# ESIMA_E-Meter_LCD.net
KiCad netlist of a schematic drawn in Altium Designer
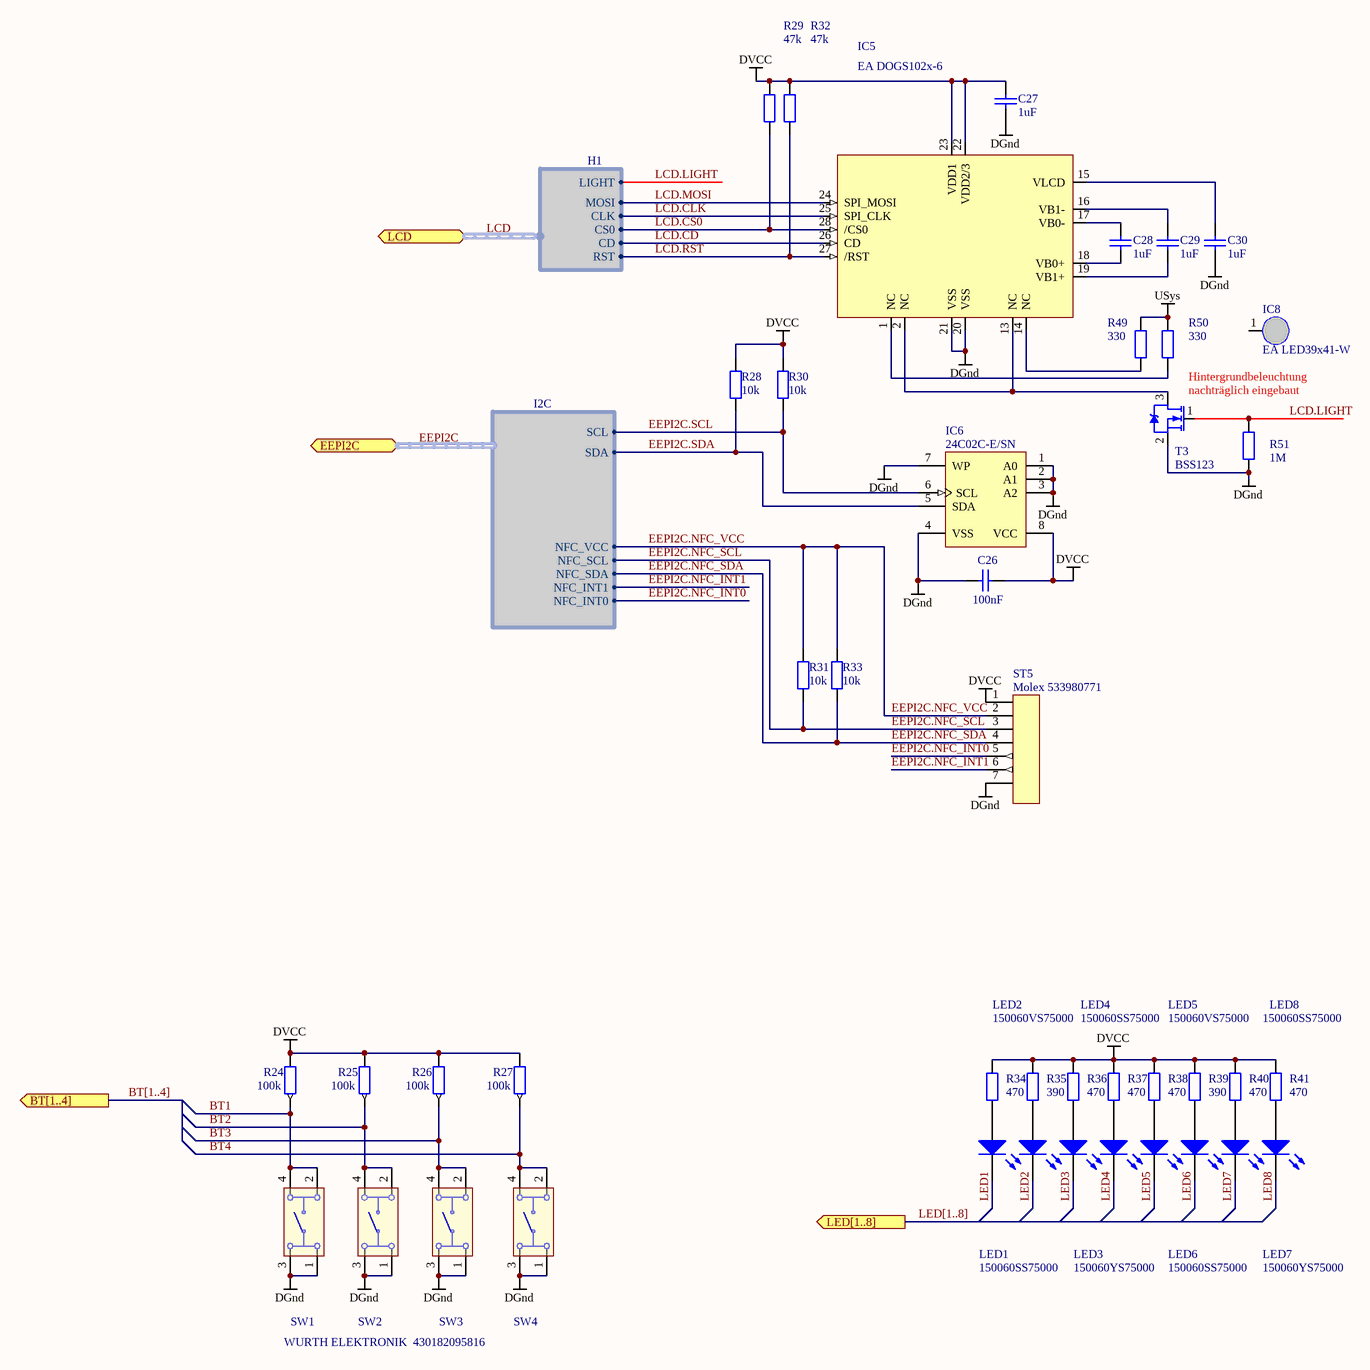
[diagram p0: ESIMA E-Meter_LCD.SchDoc]

(export (version "E")
  (design (tool "Eeschema 10.0.6"))
  (components
    (comp (ref "C26")
      (value "100nF")
      (footprint "CAPC1608N")
      (description "CAPC1608 (C0603)")
      (libsource (lib "JM_Kondensatoren") (part "CAPC1608 (C0603)"))
    )
    (comp (ref "C27")
      (value "1uF")
      (footprint "CAPC2012N")
      (description "CAPC2012 (C0805)")
      (libsource (lib "JM_Kondensatoren") (part "CAPC2012 (C0805)"))
    )
    (comp (ref "C28")
      (value "1uF")
      (footprint "CAPC2012N")
      (description "CAPC2012 (C0805)")
      (libsource (lib "JM_Kondensatoren") (part "CAPC2012 (C0805)"))
    )
    (comp (ref "C29")
      (value "1uF")
      (footprint "CAPC2012N")
      (description "CAPC2012 (C0805)")
      (libsource (lib "JM_Kondensatoren") (part "CAPC2012 (C0805)"))
    )
    (comp (ref "C30")
      (value "1uF")
      (footprint "CAPC2012N")
      (description "CAPC2012 (C0805)")
      (libsource (lib "JM_Kondensatoren") (part "CAPC2012 (C0805)"))
    )
    (comp (ref "IC5")
      (value "EA DOGS102x-6")
      (footprint "EA DOGS102x-6")
      (description "LCD Graphic Display 102*64 Dots SPI-Interface")
      (libsource (lib "JM_Halbleiter") (part "EA DOGS102x-6"))
    )
    (comp (ref "IC6")
      (value "24C02C-E/SN")
      (footprint "SOIC-SN8_N")
      (description "2Kbit, 400kHz, 5V, I2C Serial EEPROM, 8-Pin SOIC 150mil, Extended Temperature")
      (libsource (lib "Microchip EEPROM I2C Serial") (part "24C02C-E/SN"))
    )
    (comp (ref "IC8")
      (value "EA LED39x41-W")
      (description "LCD-Hintergrundbeleuchtung, Part von EA DOGS102x-6")
      (libsource (lib "JM_Elektromechanik") (part "Passmarke 1mm"))
    )
    (comp (ref "LED1")
      (value "150060SS75000")
      (footprint "0603")
      (description "LED, 0603, SUP. ROT, 60MCD, 630NM")
      (libsource (lib "WL-SMCW") (part "WL-SMCW 0603  150060SS75000"))
    )
    (comp (ref "LED2")
      (value "150060VS75000")
      (footprint "0603")
      (description "LED, 0603, GRÜN, 40MCD, 570NM")
      (libsource (lib "WL-SMCW") (part "WL-SMCW 0603  150060VS75000"))
    )
    (comp (ref "LED3")
      (value "150060YS75000")
      (footprint "0603")
      (description "LED, 0603, GELB, 120MCD, 590NM")
      (libsource (lib "WL-SMCW") (part "WL-SMCW 0603  150060YS75000"))
    )
    (comp (ref "LED4")
      (value "150060SS75000")
      (footprint "0603")
      (description "LED, 0603, SUP. ROT, 60MCD, 630NM")
      (libsource (lib "WL-SMCW") (part "WL-SMCW 0603  150060SS75000"))
    )
    (comp (ref "LED5")
      (value "150060VS75000")
      (footprint "0603")
      (description "LED, 0603, SUP. ROT, 60MCD, 630NM")
      (libsource (lib "WL-SMCW") (part "WL-SMCW 0603  150060VS75000"))
    )
    (comp (ref "LED6")
      (value "150060SS75000")
      (footprint "0603")
      (description "LED, 0603, GRÜN, 40MCD, 570NM")
      (libsource (lib "WL-SMCW") (part "WL-SMCW 0603  150060SS75000"))
    )
    (comp (ref "LED7")
      (value "150060YS75000")
      (footprint "0603")
      (description "LED, 0603, GELB, 120MCD, 590NM")
      (libsource (lib "WL-SMCW") (part "WL-SMCW 0603  150060YS75000"))
    )
    (comp (ref "LED8")
      (value "150060SS75000")
      (footprint "0603")
      (description "LED, 0603, SUP. ROT, 60MCD, 630NM")
      (libsource (lib "WL-SMCW") (part "WL-SMCW 0603  150060SS75000"))
    )
    (comp (ref "R24")
      (value "100k")
      (footprint "RESC1608N")
      (description "RESC1608 (R0603)")
      (libsource (lib "") (part "RESC1608 (R0603)_1"))
    )
    (comp (ref "R25")
      (value "100k")
      (footprint "RESC1608N")
      (description "RESC1608 (R0603)")
      (libsource (lib "") (part "RESC1608 (R0603)_1"))
    )
    (comp (ref "R26")
      (value "100k")
      (footprint "RESC1608N")
      (description "RESC1608 (R0603)")
      (libsource (lib "") (part "RESC1608 (R0603)_1"))
    )
    (comp (ref "R27")
      (value "100k")
      (footprint "RESC1608N")
      (description "RESC1608 (R0603)")
      (libsource (lib "") (part "RESC1608 (R0603)_1"))
    )
    (comp (ref "R28")
      (value "10k")
      (footprint "RESC1608N")
      (description "RESC1608 (R0603)")
      (libsource (lib "JM_Widerstaende") (part "RESC1608 (R0603)"))
    )
    (comp (ref "R29")
      (value "47k")
      (footprint "RESC1608N")
      (description "RESC1608 (R0603)")
      (libsource (lib "") (part "RESC1608 (R0603)_3"))
    )
    (comp (ref "R30")
      (value "10k")
      (footprint "RESC1608N")
      (description "RESC1608 (R0603)")
      (libsource (lib "JM_Widerstaende") (part "RESC1608 (R0603)"))
    )
    (comp (ref "R31")
      (value "10k")
      (footprint "RESC1608N")
      (description "RESC1608 (R0603)")
      (libsource (lib "JM_Widerstaende") (part "RESC1608 (R0603)"))
    )
    (comp (ref "R32")
      (value "47k")
      (footprint "RESC1608N")
      (description "RESC1608 (R0603)")
      (libsource (lib "") (part "RESC1608 (R0603)_3"))
    )
    (comp (ref "R33")
      (value "10k")
      (footprint "RESC1608N")
      (description "RESC1608 (R0603)")
      (libsource (lib "JM_Widerstaende") (part "RESC1608 (R0603)"))
    )
    (comp (ref "R34")
      (value "470")
      (footprint "RESC1608N")
      (description "RESC1608 (R0603)")
      (libsource (lib "") (part "RESC1608 (R0603)_2"))
    )
    (comp (ref "R35")
      (value "390")
      (footprint "RESC1608N")
      (description "RESC1608 (R0603)")
      (libsource (lib "") (part "RESC1608 (R0603)_2"))
    )
    (comp (ref "R36")
      (value "470")
      (footprint "RESC1608N")
      (description "RESC1608 (R0603)")
      (libsource (lib "") (part "RESC1608 (R0603)_2"))
    )
    (comp (ref "R37")
      (value "470")
      (footprint "RESC1608N")
      (description "RESC1608 (R0603)")
      (libsource (lib "") (part "RESC1608 (R0603)_2"))
    )
    (comp (ref "R38")
      (value "470")
      (footprint "RESC1608N")
      (description "RESC1608 (R0603)")
      (libsource (lib "") (part "RESC1608 (R0603)_2"))
    )
    (comp (ref "R39")
      (value "390")
      (footprint "RESC1608N")
      (description "RESC1608 (R0603)")
      (libsource (lib "") (part "RESC1608 (R0603)_2"))
    )
    (comp (ref "R40")
      (value "470")
      (footprint "RESC1608N")
      (description "RESC1608 (R0603)")
      (libsource (lib "") (part "RESC1608 (R0603)_2"))
    )
    (comp (ref "R41")
      (value "470")
      (footprint "RESC1608N")
      (description "RESC1608 (R0603)")
      (libsource (lib "") (part "RESC1608 (R0603)_2"))
    )
    (comp (ref "R49")
      (value "330")
      (footprint "RESC1608N")
      (description "RESC1608 (R0603)")
      (libsource (lib "") (part "RESC1608 (R0603)_3"))
    )
    (comp (ref "R50")
      (value "330")
      (footprint "RESC1608N")
      (description "RESC1608 (R0603)")
      (libsource (lib "") (part "RESC1608 (R0603)_3"))
    )
    (comp (ref "R51")
      (value "1M")
      (footprint "RESC1608N")
      (description "RESC1608 (R0603)")
      (libsource (lib "") (part "RESC1608 (R0603)_3"))
    )
    (comp (ref "ST5")
      (value "Molex 533980771")
      (footprint "Molex 533980771")
      (description "Molex Pico 7Pol Blade SMD gerade 533980771")
      (libsource (lib "JM_Elektromechanik") (part "Molex 533980771"))
    )
    (comp (ref "SW1")
      (value "WURTH ELEKTRONIK  430182095816")
      (footprint "430152130826")
      (description "WS-TASV SMD Tact Switch 6X6 mm")
      (fields
        (field (name "MANUFACTURER") "Würth Elektronik eiSos GmbH & Co.KG")
        (field (name "PARTNO") "430152130826")
        (field (name "CREAT BY") "Karrer Zheng")
      )
      (libsource (lib "Kurzhubtaster") (part "WE-Tact Switches WS-TASV 430152130826"))
    )
    (comp (ref "SW2")
      (value "WURTH ELEKTRONIK  430182095816")
      (footprint "430152130826")
      (description "WS-TASV SMD Tact Switch 6X6 mm")
      (fields
        (field (name "MANUFACTURER") "Würth Elektronik eiSos GmbH & Co.KG")
        (field (name "PARTNO") "430152130826")
        (field (name "CREAT BY") "Karrer Zheng")
      )
      (libsource (lib "Kurzhubtaster") (part "WE-Tact Switches WS-TASV 430152130826"))
    )
    (comp (ref "SW3")
      (value "WURTH ELEKTRONIK  430182095816")
      (footprint "430152130826")
      (description "WS-TASV SMD Tact Switch 6X6 mm")
      (fields
        (field (name "MANUFACTURER") "Würth Elektronik eiSos GmbH & Co.KG")
        (field (name "PARTNO") "430152130826")
        (field (name "CREAT BY") "Karrer Zheng")
      )
      (libsource (lib "Kurzhubtaster") (part "WE-Tact Switches WS-TASV 430152130826"))
    )
    (comp (ref "SW4")
      (value "WURTH ELEKTRONIK  430182095816")
      (footprint "430152130826")
      (description "WS-TASV SMD Tact Switch 6X6 mm")
      (fields
        (field (name "MANUFACTURER") "Würth Elektronik eiSos GmbH & Co.KG")
        (field (name "PARTNO") "430152130826")
        (field (name "CREAT BY") "Karrer Zheng")
      )
      (libsource (lib "Kurzhubtaster") (part "WE-Tact Switches WS-TASV 430152130826"))
    )
    (comp (ref "T3")
      (value "BSS123")
      (footprint "SOT23-3N")
      (description "MOSFET N-Kanal SOT-23")
      (fields (field (name "09_ERSTELLER") "HSG Jürgen Merz"))
      (libsource (lib "HSG-IMIT_JuergenMerz") (part "MOSFET N-Kanal SOT-23"))
    )
  )
  (nets
    (net (code "3") (name "/BT1") (class "Default")
      (node (ref "R24") (pin "1") (pinfunction "1_1") (pintype "output"))
      (node (ref "SW1") (pin "2") (pinfunction "2_2") (pintype "passive"))
      (node (ref "SW1") (pin "4") (pinfunction "4_4") (pintype "passive"))
    )
    (net (code "4") (name "/BT2") (class "Default")
      (node (ref "R25") (pin "1") (pinfunction "1_1") (pintype "output"))
      (node (ref "SW2") (pin "2") (pinfunction "2_2") (pintype "passive"))
      (node (ref "SW2") (pin "4") (pinfunction "4_4") (pintype "passive"))
    )
    (net (code "5") (name "/BT3") (class "Default")
      (node (ref "R26") (pin "1") (pinfunction "1_1") (pintype "output"))
      (node (ref "SW3") (pin "2") (pinfunction "2_2") (pintype "passive"))
      (node (ref "SW3") (pin "4") (pinfunction "4_4") (pintype "passive"))
    )
    (net (code "6") (name "/BT4") (class "Default")
      (node (ref "R27") (pin "1") (pinfunction "1_1") (pintype "output"))
      (node (ref "SW4") (pin "2") (pinfunction "2_2") (pintype "passive"))
      (node (ref "SW4") (pin "4") (pinfunction "4_4") (pintype "passive"))
    )
    (net (code "8") (name "/EEPI2C.NFC_INT0") (class "Default")
      (node (ref "ST5") (pin "5") (pinfunction "5_5") (pintype "output"))
    )
    (net (code "9") (name "/EEPI2C.NFC_INT1") (class "Default")
      (node (ref "ST5") (pin "6") (pinfunction "6_6") (pintype "output"))
    )
    (net (code "10") (name "/EEPI2C.NFC_SCL") (class "Default")
      (node (ref "R31") (pin "1") (pinfunction "1_1") (pintype "passive"))
      (node (ref "ST5") (pin "3") (pinfunction "3_3") (pintype "passive"))
    )
    (net (code "11") (name "/EEPI2C.NFC_SDA") (class "Default")
      (node (ref "R33") (pin "1") (pinfunction "1_1") (pintype "passive"))
      (node (ref "ST5") (pin "4") (pinfunction "4_4") (pintype "passive"))
    )
    (net (code "12") (name "/EEPI2C.NFC_VCC") (class "Default")
      (node (ref "R31") (pin "2") (pinfunction "2_2") (pintype "passive"))
      (node (ref "R33") (pin "2") (pinfunction "2_2") (pintype "passive"))
      (node (ref "ST5") (pin "2") (pinfunction "2_2") (pintype "passive"))
    )
    (net (code "13") (name "/EEPI2C.SCL") (class "Default")
      (node (ref "IC6") (pin "6") (pinfunction "SCL_6") (pintype "input"))
      (node (ref "R30") (pin "1") (pinfunction "1_1") (pintype "passive"))
    )
    (net (code "14") (name "/EEPI2C.SDA") (class "Default")
      (node (ref "IC6") (pin "5") (pinfunction "SDA_5") (pintype "open_collector"))
      (node (ref "R28") (pin "1") (pinfunction "1_1") (pintype "passive"))
    )
    (net (code "16") (name "/LCD.CD") (class "Default")
      (node (ref "IC5") (pin "26") (pinfunction "CD_26") (pintype "input"))
    )
    (net (code "17") (name "/LCD.CLK") (class "Default")
      (node (ref "IC5") (pin "25") (pinfunction "SPI_CLK_25") (pintype "input"))
    )
    (net (code "18") (name "/LCD.CS0") (class "Default")
      (node (ref "IC5") (pin "28") (pinfunction "/CS0_28") (pintype "input"))
      (node (ref "R29") (pin "2") (pinfunction "2_2") (pintype "passive"))
    )
    (net (code "19") (name "/LCD.LIGHT") (class "Default")
      (node (ref "R51") (pin "1") (pinfunction "1_1") (pintype "passive"))
      (node (ref "T3") (pin "1") (pinfunction "G_1") (pintype "passive"))
    )
    (net (code "20") (name "/LCD.MOSI") (class "Default")
      (node (ref "IC5") (pin "24") (pinfunction "SPI_MOSI_24") (pintype "input"))
    )
    (net (code "21") (name "/LCD.RST") (class "Default")
      (node (ref "IC5") (pin "27") (pinfunction "/RST_27") (pintype "input"))
      (node (ref "R32") (pin "2") (pinfunction "2_2") (pintype "passive"))
    )
    (net (code "22") (name "/LED1") (class "Default")
      (node (ref "LED1") (pin "1") (pinfunction "C_1") (pintype "passive"))
    )
    (net (code "23") (name "/LED2") (class "Default")
      (node (ref "LED2") (pin "1") (pinfunction "C_1") (pintype "passive"))
    )
    (net (code "24") (name "/LED3") (class "Default")
      (node (ref "LED3") (pin "1") (pinfunction "C_1") (pintype "passive"))
    )
    (net (code "25") (name "/LED4") (class "Default")
      (node (ref "LED4") (pin "1") (pinfunction "C_1") (pintype "passive"))
    )
    (net (code "26") (name "/LED5") (class "Default")
      (node (ref "LED6") (pin "1") (pinfunction "C_1") (pintype "passive"))
    )
    (net (code "27") (name "/LED6") (class "Default")
      (node (ref "LED5") (pin "1") (pinfunction "C_1") (pintype "passive"))
    )
    (net (code "28") (name "/LED7") (class "Default")
      (node (ref "LED7") (pin "1") (pinfunction "C_1") (pintype "passive"))
    )
    (net (code "29") (name "/LED8") (class "Default")
      (node (ref "LED8") (pin "1") (pinfunction "C_1") (pintype "passive"))
    )
    (net (code "32") (name "DGnd") (class "Default")
      (node (ref "C26") (pin "1") (pinfunction "1_1") (pintype "passive"))
      (node (ref "C27") (pin "1") (pinfunction "1_1") (pintype "passive"))
      (node (ref "C30") (pin "1") (pinfunction "1_1") (pintype "passive"))
      (node (ref "IC5") (pin "20") (pinfunction "VSS_20") (pintype "power_in"))
      (node (ref "IC5") (pin "21") (pinfunction "VSS_21") (pintype "power_in"))
      (node (ref "IC6") (pin "1") (pinfunction "A0_1") (pintype "passive"))
      (node (ref "IC6") (pin "2") (pinfunction "A1_2") (pintype "passive"))
      (node (ref "IC6") (pin "3") (pinfunction "A2_3") (pintype "passive"))
      (node (ref "IC6") (pin "4") (pinfunction "VSS_4") (pintype "power_in"))
      (node (ref "IC6") (pin "7") (pinfunction "WP_7") (pintype "passive"))
      (node (ref "R51") (pin "2") (pinfunction "2_2") (pintype "passive"))
      (node (ref "ST5") (pin "7") (pinfunction "7_7") (pintype "passive"))
      (node (ref "SW1") (pin "1") (pinfunction "1_1") (pintype "passive"))
      (node (ref "SW1") (pin "3") (pinfunction "3_3") (pintype "passive"))
      (node (ref "SW2") (pin "1") (pinfunction "1_1") (pintype "passive"))
      (node (ref "SW2") (pin "3") (pinfunction "3_3") (pintype "passive"))
      (node (ref "SW3") (pin "1") (pinfunction "1_1") (pintype "passive"))
      (node (ref "SW3") (pin "3") (pinfunction "3_3") (pintype "passive"))
      (node (ref "SW4") (pin "1") (pinfunction "1_1") (pintype "passive"))
      (node (ref "SW4") (pin "3") (pinfunction "3_3") (pintype "passive"))
      (node (ref "T3") (pin "2") (pinfunction "S_2") (pintype "passive"))
    )
    (net (code "33") (name "DVCC") (class "Default")
      (node (ref "C26") (pin "2") (pinfunction "2_2") (pintype "passive"))
      (node (ref "C27") (pin "2") (pinfunction "2_2") (pintype "passive"))
      (node (ref "IC5") (pin "22") (pinfunction "VDD2/3_22") (pintype "power_in"))
      (node (ref "IC5") (pin "23") (pinfunction "VDD1_23") (pintype "power_in"))
      (node (ref "IC6") (pin "8") (pinfunction "VCC_8") (pintype "power_in"))
      (node (ref "R24") (pin "2") (pinfunction "2_2") (pintype "passive"))
      (node (ref "R25") (pin "2") (pinfunction "2_2") (pintype "passive"))
      (node (ref "R26") (pin "2") (pinfunction "2_2") (pintype "passive"))
      (node (ref "R27") (pin "2") (pinfunction "2_2") (pintype "passive"))
      (node (ref "R28") (pin "2") (pinfunction "2_2") (pintype "passive"))
      (node (ref "R29") (pin "1") (pinfunction "1_1") (pintype "passive"))
      (node (ref "R30") (pin "2") (pinfunction "2_2") (pintype "passive"))
      (node (ref "R32") (pin "1") (pinfunction "1_1") (pintype "passive"))
      (node (ref "R34") (pin "1") (pinfunction "1_1") (pintype "passive"))
      (node (ref "R35") (pin "1") (pinfunction "1_1") (pintype "passive"))
      (node (ref "R36") (pin "1") (pinfunction "1_1") (pintype "passive"))
      (node (ref "R37") (pin "1") (pinfunction "1_1") (pintype "passive"))
      (node (ref "R38") (pin "1") (pinfunction "1_1") (pintype "passive"))
      (node (ref "R39") (pin "1") (pinfunction "1_1") (pintype "passive"))
      (node (ref "R40") (pin "1") (pinfunction "1_1") (pintype "passive"))
      (node (ref "R41") (pin "1") (pinfunction "1_1") (pintype "passive"))
      (node (ref "ST5") (pin "1") (pinfunction "1_1") (pintype "passive"))
    )
    (net (code "34") (name "Net-(IC5-NC-Pad1)") (class "Default")
      (node (ref "IC5") (pin "1") (pinfunction "NC_1") (pintype "passive"))
      (node (ref "R50") (pin "2") (pinfunction "2_2") (pintype "passive"))
    )
    (net (code "35") (name "Net-(IC5-NC-Pad14)") (class "Default")
      (node (ref "IC5") (pin "14") (pinfunction "NC_14") (pintype "passive"))
      (node (ref "R49") (pin "2") (pinfunction "2_2") (pintype "passive"))
    )
    (net (code "36") (name "Net-(IC5-VB0+)") (class "Default")
      (node (ref "C28") (pin "1") (pinfunction "1_1") (pintype "passive"))
      (node (ref "IC5") (pin "18") (pinfunction "VB0+_18") (pintype "passive"))
    )
    (net (code "37") (name "Net-(IC5-VB0-)") (class "Default")
      (node (ref "C28") (pin "2") (pinfunction "2_2") (pintype "passive"))
      (node (ref "IC5") (pin "17") (pinfunction "VB0-_17") (pintype "passive"))
    )
    (net (code "38") (name "Net-(IC5-VB1+)") (class "Default")
      (node (ref "C29") (pin "1") (pinfunction "1_1") (pintype "passive"))
      (node (ref "IC5") (pin "19") (pinfunction "VB1+_19") (pintype "passive"))
    )
    (net (code "39") (name "Net-(IC5-VB1-)") (class "Default")
      (node (ref "C29") (pin "2") (pinfunction "2_2") (pintype "passive"))
      (node (ref "IC5") (pin "16") (pinfunction "VB1-_16") (pintype "passive"))
    )
    (net (code "40") (name "Net-(IC5-VLCD)") (class "Default")
      (node (ref "C30") (pin "2") (pinfunction "2_2") (pintype "passive"))
      (node (ref "IC5") (pin "15") (pinfunction "VLCD_15") (pintype "passive"))
    )
    (net (code "41") (name "Net-(LED1-A)") (class "Default")
      (node (ref "LED1") (pin "2") (pinfunction "A_2") (pintype "passive"))
      (node (ref "R34") (pin "2") (pinfunction "2_2") (pintype "passive"))
    )
    (net (code "42") (name "Net-(LED2-A)") (class "Default")
      (node (ref "LED2") (pin "2") (pinfunction "A_2") (pintype "passive"))
      (node (ref "R35") (pin "2") (pinfunction "2_2") (pintype "passive"))
    )
    (net (code "43") (name "Net-(LED3-A)") (class "Default")
      (node (ref "LED3") (pin "2") (pinfunction "A_2") (pintype "passive"))
      (node (ref "R36") (pin "2") (pinfunction "2_2") (pintype "passive"))
    )
    (net (code "44") (name "Net-(LED4-A)") (class "Default")
      (node (ref "LED4") (pin "2") (pinfunction "A_2") (pintype "passive"))
      (node (ref "R37") (pin "2") (pinfunction "2_2") (pintype "passive"))
    )
    (net (code "45") (name "Net-(LED5-A)") (class "Default")
      (node (ref "LED5") (pin "2") (pinfunction "A_2") (pintype "passive"))
      (node (ref "R39") (pin "2") (pinfunction "2_2") (pintype "passive"))
    )
    (net (code "46") (name "Net-(LED6-A)") (class "Default")
      (node (ref "LED6") (pin "2") (pinfunction "A_2") (pintype "passive"))
      (node (ref "R38") (pin "2") (pinfunction "2_2") (pintype "passive"))
    )
    (net (code "47") (name "Net-(LED7-A)") (class "Default")
      (node (ref "LED7") (pin "2") (pinfunction "A_2") (pintype "passive"))
      (node (ref "R40") (pin "2") (pinfunction "2_2") (pintype "passive"))
    )
    (net (code "48") (name "Net-(LED8-A)") (class "Default")
      (node (ref "LED8") (pin "2") (pinfunction "A_2") (pintype "passive"))
      (node (ref "R41") (pin "2") (pinfunction "2_2") (pintype "passive"))
    )
    (net (code "49") (name "Net-(T3-D)") (class "Default")
      (node (ref "IC5") (pin "13") (pinfunction "NC_13") (pintype "passive"))
      (node (ref "IC5") (pin "2") (pinfunction "NC_2") (pintype "passive"))
      (node (ref "T3") (pin "3") (pinfunction "D_3") (pintype "passive"))
    )
    (net (code "50") (name "USys") (class "Default")
      (node (ref "R49") (pin "1") (pinfunction "1_1") (pintype "passive"))
      (node (ref "R50") (pin "1") (pinfunction "1_1") (pintype "passive"))
    )
    (net (code "51") (name "unconnected-(IC8-Pad1)") (class "Default")
      (node (ref "IC8") (pin "1") (pinfunction "1_1") (pintype "passive"))
    )
    (net (code "52") (name "unconnected-(ST5-Pad8)") (class "Default")
      (node (ref "ST5") (pin "8") (pinfunction "8_8") (pintype "passive"))
    )
    (net (code "53") (name "unconnected-(ST5-Pad9)") (class "Default")
      (node (ref "ST5") (pin "9") (pinfunction "9_9") (pintype "passive"))
    )
  )
)
